# SD.net
KiCad netlist of a schematic drawn in Altium Designer
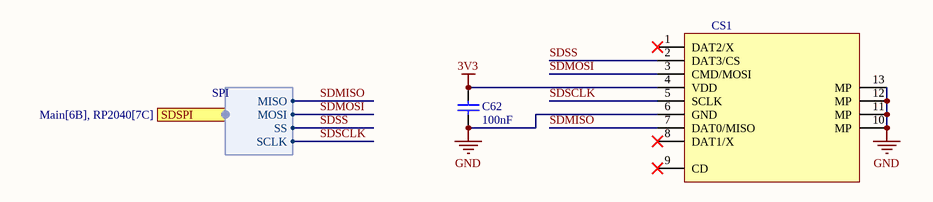
[diagram p0: SD.SchDoc]

(export (version "E")
  (design (tool "Eeschema 10.0.6"))
  (components
    (comp (ref "C62")
      (value "100nF")
      (footprint "WCAP-CSGP_0603_L1.6W0.8H0.8_Reflow")
      (description "WCAP-CSGP Multilayer Ceramic Chip Capacitor, General Purpose, size 0603, X7R, 100nF, 50VDC")
      (fields
        (field (name "MANUFACTURER PART NUMBER") "885012206095")
        (field (name "MANUFACTURER") "Wurth Elektronik")
      )
      (libsource (lib "Altium_WCAP-CSGP (rev22f)") (part "885012206095"))
    )
    (comp (ref "CS1")
      (value "MicroSD TF Card")
      (footprint "MicroSD TF Card Slot")
      (description "SHOU HAN TF-CARD H1.8")
      (libsource (lib "Custom Components") (part "MicroSD TF Card"))
    )
  )
  (nets
    (net (code "2") (name "/SDMISO") (class "Default")
      (node (ref "CS1") (pin "7") (pinfunction "DAT0/MISO_7") (pintype "passive"))
    )
    (net (code "3") (name "/SDMOSI") (class "Default")
      (node (ref "CS1") (pin "3") (pinfunction "CMD/MOSI_3") (pintype "passive"))
    )
    (net (code "4") (name "/SDSCLK") (class "Default")
      (node (ref "CS1") (pin "5") (pinfunction "SCLK_5") (pintype "passive"))
    )
    (net (code "5") (name "/SDSS") (class "Default")
      (node (ref "CS1") (pin "2") (pinfunction "DAT3/CS_2") (pintype "passive"))
    )
    (net (code "7") (name "3V3") (class "Default")
      (node (ref "C62") (pin "2") (pinfunction "2_2") (pintype "passive"))
      (node (ref "CS1") (pin "4") (pinfunction "VDD_4") (pintype "passive"))
    )
    (net (code "8") (name "GND") (class "Default")
      (node (ref "C62") (pin "1") (pinfunction "1_1") (pintype "passive"))
      (node (ref "CS1") (pin "10") (pinfunction "MP_10") (pintype "passive"))
      (node (ref "CS1") (pin "11") (pinfunction "MP_11") (pintype "passive"))
      (node (ref "CS1") (pin "12") (pinfunction "MP_12") (pintype "passive"))
      (node (ref "CS1") (pin "13") (pinfunction "MP_13") (pintype "passive"))
      (node (ref "CS1") (pin "6") (pinfunction "GND_6") (pintype "passive"))
    )
    (net (code "9") (name "unconnected-(CS1-CD-Pad9)") (class "Default")
      (node (ref "CS1") (pin "9") (pinfunction "CD_9") (pintype "passive+no_connect"))
    )
    (net (code "10") (name "unconnected-(CS1-DAT1{slash}X-Pad8)") (class "Default")
      (node (ref "CS1") (pin "8") (pinfunction "DAT1/X_8") (pintype "passive+no_connect"))
    )
    (net (code "11") (name "unconnected-(CS1-DAT2{slash}X-Pad1)") (class "Default")
      (node (ref "CS1") (pin "1") (pinfunction "DAT2/X_1") (pintype "passive+no_connect"))
    )
  )
)
